# ESP8266_D1_Mini_Breakout.net
KiCad netlist of a schematic drawn in EAGLE
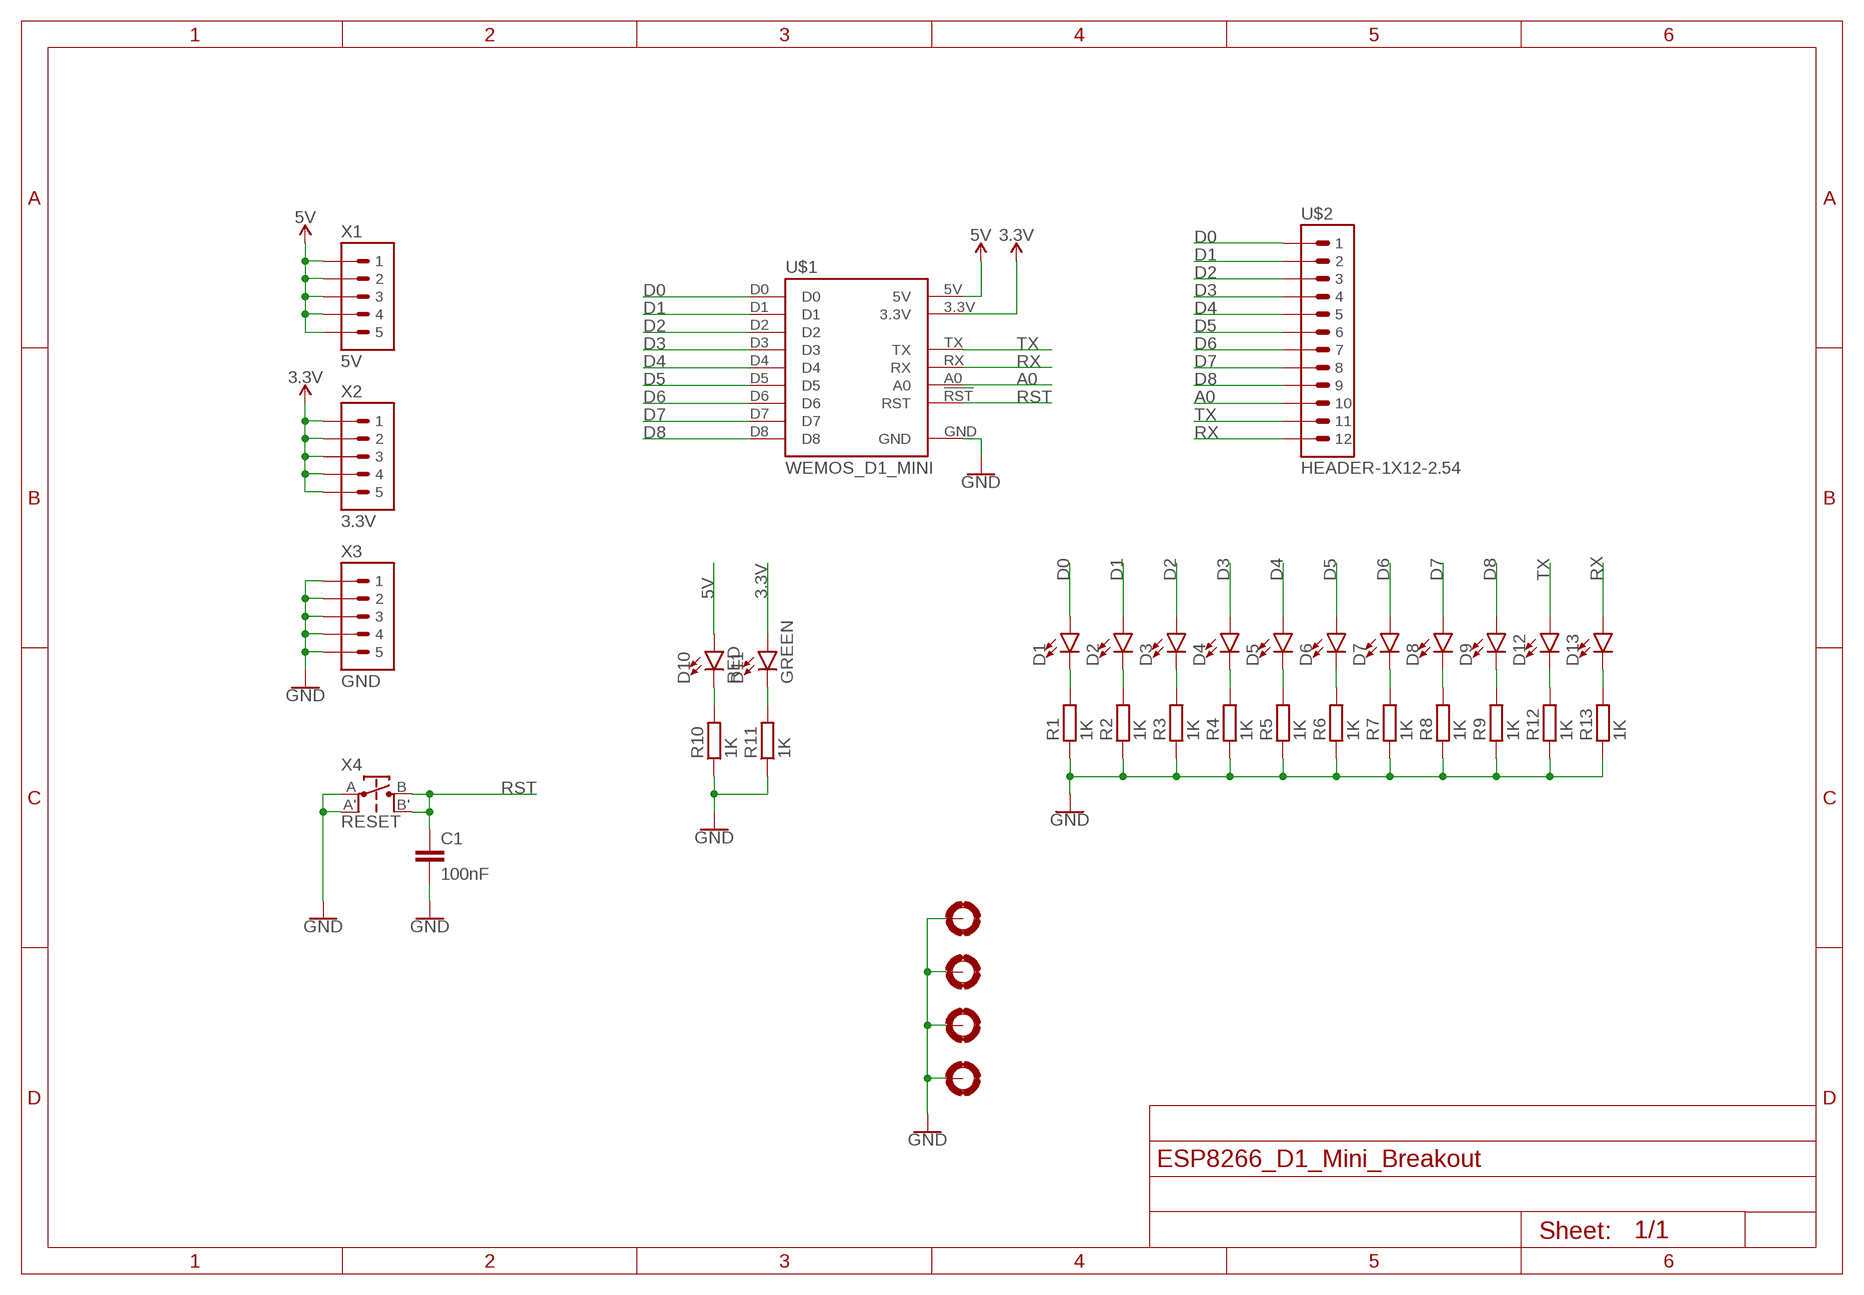
[diagram p0: schematic, sheet 1]

(export (version "E")
  (design (tool "Eeschema 10.0.6"))
  (components
    (comp (ref "C1")
      (value "100nF")
      (footprint "eagle-import:C0603")
      (libsource (lib "eagle-import") (part "CAPC0603"))
    )
    (comp (ref "D1")
      (value "LED0603")
      (footprint "eagle-import:LED0603")
      (libsource (lib "eagle-import") (part "LED0603"))
    )
    (comp (ref "D2")
      (value "LED0603")
      (footprint "eagle-import:LED0603")
      (libsource (lib "eagle-import") (part "LED0603"))
    )
    (comp (ref "D3")
      (value "LED0603")
      (footprint "eagle-import:LED0603")
      (libsource (lib "eagle-import") (part "LED0603"))
    )
    (comp (ref "D4")
      (value "LED0603")
      (footprint "eagle-import:LED0603")
      (libsource (lib "eagle-import") (part "LED0603"))
    )
    (comp (ref "D5")
      (value "LED0603")
      (footprint "eagle-import:LED0603")
      (libsource (lib "eagle-import") (part "LED0603"))
    )
    (comp (ref "D6")
      (value "LED0603")
      (footprint "eagle-import:LED0603")
      (libsource (lib "eagle-import") (part "LED0603"))
    )
    (comp (ref "D7")
      (value "LED0603")
      (footprint "eagle-import:LED0603")
      (libsource (lib "eagle-import") (part "LED0603"))
    )
    (comp (ref "D8")
      (value "LED0603")
      (footprint "eagle-import:LED0603")
      (libsource (lib "eagle-import") (part "LED0603"))
    )
    (comp (ref "D9")
      (value "LED0603")
      (footprint "eagle-import:LED0603")
      (libsource (lib "eagle-import") (part "LED0603"))
    )
    (comp (ref "D10")
      (value "RED")
      (footprint "eagle-import:LED0603")
      (libsource (lib "eagle-import") (part "LED0603"))
    )
    (comp (ref "D11")
      (value "GREEN")
      (footprint "eagle-import:LED0603")
      (libsource (lib "eagle-import") (part "LED0603"))
    )
    (comp (ref "D12")
      (value "LED0603")
      (footprint "eagle-import:LED0603")
      (libsource (lib "eagle-import") (part "LED0603"))
    )
    (comp (ref "D13")
      (value "LED0603")
      (footprint "eagle-import:LED0603")
      (libsource (lib "eagle-import") (part "LED0603"))
    )
    (comp (ref "H1")
      (value "MOUNTHOLE-PAD3.2")
      (footprint "eagle-import:3.2-PAD")
      (libsource (lib "eagle-import") (part "MOUNTHOLE-PAD3.2"))
    )
    (comp (ref "H2")
      (value "MOUNTHOLE-PAD3.2")
      (footprint "eagle-import:3.2-PAD")
      (libsource (lib "eagle-import") (part "MOUNTHOLE-PAD3.2"))
    )
    (comp (ref "H3")
      (value "MOUNTHOLE-PAD3.2")
      (footprint "eagle-import:3.2-PAD")
      (libsource (lib "eagle-import") (part "MOUNTHOLE-PAD3.2"))
    )
    (comp (ref "H4")
      (value "MOUNTHOLE-PAD3.2")
      (footprint "eagle-import:3.2-PAD")
      (libsource (lib "eagle-import") (part "MOUNTHOLE-PAD3.2"))
    )
    (comp (ref "R1")
      (value "1K")
      (footprint "eagle-import:R0603")
      (libsource (lib "eagle-import") (part "RESISTOR0603"))
    )
    (comp (ref "R2")
      (value "1K")
      (footprint "eagle-import:R0603")
      (libsource (lib "eagle-import") (part "RESISTOR0603"))
    )
    (comp (ref "R3")
      (value "1K")
      (footprint "eagle-import:R0603")
      (libsource (lib "eagle-import") (part "RESISTOR0603"))
    )
    (comp (ref "R4")
      (value "1K")
      (footprint "eagle-import:R0603")
      (libsource (lib "eagle-import") (part "RESISTOR0603"))
    )
    (comp (ref "R5")
      (value "1K")
      (footprint "eagle-import:R0603")
      (libsource (lib "eagle-import") (part "RESISTOR0603"))
    )
    (comp (ref "R6")
      (value "1K")
      (footprint "eagle-import:R0603")
      (libsource (lib "eagle-import") (part "RESISTOR0603"))
    )
    (comp (ref "R7")
      (value "1K")
      (footprint "eagle-import:R0603")
      (libsource (lib "eagle-import") (part "RESISTOR0603"))
    )
    (comp (ref "R8")
      (value "1K")
      (footprint "eagle-import:R0603")
      (libsource (lib "eagle-import") (part "RESISTOR0603"))
    )
    (comp (ref "R9")
      (value "1K")
      (footprint "eagle-import:R0603")
      (libsource (lib "eagle-import") (part "RESISTOR0603"))
    )
    (comp (ref "R10")
      (value "1K")
      (footprint "eagle-import:R0603")
      (libsource (lib "eagle-import") (part "RESISTOR0603"))
    )
    (comp (ref "R11")
      (value "1K")
      (footprint "eagle-import:R0603")
      (libsource (lib "eagle-import") (part "RESISTOR0603"))
    )
    (comp (ref "R12")
      (value "1K")
      (footprint "eagle-import:R0603")
      (libsource (lib "eagle-import") (part "RESISTOR0603"))
    )
    (comp (ref "R13")
      (value "1K")
      (footprint "eagle-import:R0603")
      (libsource (lib "eagle-import") (part "RESISTOR0603"))
    )
    (comp (ref "U$1")
      (value "WEMOS_D1_MINI")
      (footprint "eagle-import:WEMOS_D1_MINI")
      (libsource (lib "eagle-import") (part "WEMOS_D1_MINI"))
    )
    (comp (ref "U$2")
      (value "HEADER-1X12-2.54")
      (footprint "eagle-import:1X12-2.54")
      (libsource (lib "eagle-import") (part "HEADER-1X12-2.54"))
    )
    (comp (ref "X1")
      (value "5V")
      (footprint "eagle-import:1X05-2.54")
      (libsource (lib "eagle-import") (part "HEADER-1X05-2.54"))
    )
    (comp (ref "X2")
      (value "3.3V")
      (footprint "eagle-import:1X05-2.54")
      (libsource (lib "eagle-import") (part "HEADER-1X05-2.54"))
    )
    (comp (ref "X3")
      (value "GND")
      (footprint "eagle-import:1X05-2.54")
      (libsource (lib "eagle-import") (part "HEADER-1X05-2.54"))
    )
    (comp (ref "X4")
      (value "RESET")
      (footprint "eagle-import:TACT-SWITCH-EVQ")
      (libsource (lib "eagle-import") (part "TACT-SWITCHEVQ"))
    )
  )
  (nets
    (net (code "1") (name "/A0") (class "Default")
      (node (ref "U$1") (pin "A0") (pinfunction "A0_A0") (pintype "bidirectional"))
      (node (ref "U$2") (pin "10") (pinfunction "10_10") (pintype "bidirectional"))
    )
    (net (code "2") (name "/D0") (class "Default")
      (node (ref "D1") (pin "A") (pinfunction "A_A") (pintype "passive"))
      (node (ref "U$1") (pin "D0") (pinfunction "D0_D0") (pintype "bidirectional"))
      (node (ref "U$2") (pin "1") (pinfunction "1_1") (pintype "passive"))
    )
    (net (code "3") (name "/D1") (class "Default")
      (node (ref "D2") (pin "A") (pinfunction "A_A") (pintype "passive"))
      (node (ref "U$1") (pin "D1") (pinfunction "D1_D1") (pintype "bidirectional"))
      (node (ref "U$2") (pin "2") (pinfunction "2_2") (pintype "passive"))
    )
    (net (code "4") (name "/D2") (class "Default")
      (node (ref "D3") (pin "A") (pinfunction "A_A") (pintype "passive"))
      (node (ref "U$1") (pin "D2") (pinfunction "D2_D2") (pintype "bidirectional"))
      (node (ref "U$2") (pin "3") (pinfunction "3_3") (pintype "passive"))
    )
    (net (code "5") (name "/D3") (class "Default")
      (node (ref "D4") (pin "A") (pinfunction "A_A") (pintype "passive"))
      (node (ref "U$1") (pin "D3") (pinfunction "D3_D3") (pintype "bidirectional"))
      (node (ref "U$2") (pin "4") (pinfunction "4_4") (pintype "passive"))
    )
    (net (code "6") (name "/D4") (class "Default")
      (node (ref "D5") (pin "A") (pinfunction "A_A") (pintype "passive"))
      (node (ref "U$1") (pin "D4") (pinfunction "D4_D4") (pintype "bidirectional"))
      (node (ref "U$2") (pin "5") (pinfunction "5_5") (pintype "passive"))
    )
    (net (code "7") (name "/D5") (class "Default")
      (node (ref "D6") (pin "A") (pinfunction "A_A") (pintype "passive"))
      (node (ref "U$1") (pin "D5") (pinfunction "D5_D5") (pintype "bidirectional"))
      (node (ref "U$2") (pin "6") (pinfunction "6_6") (pintype "passive"))
    )
    (net (code "8") (name "/D6") (class "Default")
      (node (ref "D7") (pin "A") (pinfunction "A_A") (pintype "passive"))
      (node (ref "U$1") (pin "D6") (pinfunction "D6_D6") (pintype "bidirectional"))
      (node (ref "U$2") (pin "7") (pinfunction "7_7") (pintype "passive"))
    )
    (net (code "9") (name "/D7") (class "Default")
      (node (ref "D8") (pin "A") (pinfunction "A_A") (pintype "passive"))
      (node (ref "U$1") (pin "D7") (pinfunction "D7_D7") (pintype "bidirectional"))
      (node (ref "U$2") (pin "8") (pinfunction "8_8") (pintype "bidirectional"))
    )
    (net (code "10") (name "/D8") (class "Default")
      (node (ref "D9") (pin "A") (pinfunction "A_A") (pintype "passive"))
      (node (ref "U$1") (pin "D8") (pinfunction "D8_D8") (pintype "bidirectional"))
      (node (ref "U$2") (pin "9") (pinfunction "9_9") (pintype "bidirectional"))
    )
    (net (code "11") (name "/RST") (class "Default")
      (node (ref "C1") (pin "1") (pinfunction "1_1") (pintype "passive"))
      (node (ref "U$1") (pin "!RST") (pinfunction "RST_!RST") (pintype "bidirectional"))
      (node (ref "X4") (pin "B") (pinfunction "B_B") (pintype "bidirectional"))
      (node (ref "X4") (pin "B'") (pinfunction "B'_B'") (pintype "bidirectional"))
    )
    (net (code "12") (name "/RX") (class "Default")
      (node (ref "D13") (pin "A") (pinfunction "A_A") (pintype "passive"))
      (node (ref "U$1") (pin "RX") (pinfunction "RX_RX") (pintype "bidirectional"))
      (node (ref "U$2") (pin "12") (pinfunction "12_12") (pintype "bidirectional"))
    )
    (net (code "13") (name "/TX") (class "Default")
      (node (ref "D12") (pin "A") (pinfunction "A_A") (pintype "passive"))
      (node (ref "U$1") (pin "TX") (pinfunction "TX_TX") (pintype "bidirectional"))
      (node (ref "U$2") (pin "11") (pinfunction "11_11") (pintype "bidirectional"))
    )
    (net (code "14") (name "3.3V") (class "Default")
      (node (ref "D11") (pin "A") (pinfunction "A_A") (pintype "passive"))
      (node (ref "U$1") (pin "3.3V") (pinfunction "3.3V_3.3V") (pintype "bidirectional"))
      (node (ref "X2") (pin "1") (pinfunction "1_1") (pintype "passive"))
      (node (ref "X2") (pin "2") (pinfunction "2_2") (pintype "passive"))
      (node (ref "X2") (pin "3") (pinfunction "3_3") (pintype "passive"))
      (node (ref "X2") (pin "4") (pinfunction "4_4") (pintype "passive"))
      (node (ref "X2") (pin "5") (pinfunction "5_5") (pintype "passive"))
    )
    (net (code "15") (name "5V") (class "Default")
      (node (ref "D10") (pin "A") (pinfunction "A_A") (pintype "passive"))
      (node (ref "U$1") (pin "5V") (pinfunction "5V_5V") (pintype "bidirectional"))
      (node (ref "X1") (pin "1") (pinfunction "1_1") (pintype "passive"))
      (node (ref "X1") (pin "2") (pinfunction "2_2") (pintype "passive"))
      (node (ref "X1") (pin "3") (pinfunction "3_3") (pintype "passive"))
      (node (ref "X1") (pin "4") (pinfunction "4_4") (pintype "passive"))
      (node (ref "X1") (pin "5") (pinfunction "5_5") (pintype "passive"))
    )
    (net (code "16") (name "GND") (class "Default")
      (node (ref "C1") (pin "2") (pinfunction "2_2") (pintype "passive"))
      (node (ref "H1") (pin "B3,2") (pinfunction "MOUNT_B3,2") (pintype "passive"))
      (node (ref "H2") (pin "B3,2") (pinfunction "MOUNT_B3,2") (pintype "passive"))
      (node (ref "H3") (pin "B3,2") (pinfunction "MOUNT_B3,2") (pintype "passive"))
      (node (ref "H4") (pin "B3,2") (pinfunction "MOUNT_B3,2") (pintype "passive"))
      (node (ref "R1") (pin "1") (pinfunction "1_1") (pintype "passive"))
      (node (ref "R10") (pin "1") (pinfunction "1_1") (pintype "passive"))
      (node (ref "R11") (pin "1") (pinfunction "1_1") (pintype "passive"))
      (node (ref "R12") (pin "1") (pinfunction "1_1") (pintype "passive"))
      (node (ref "R13") (pin "1") (pinfunction "1_1") (pintype "passive"))
      (node (ref "R2") (pin "1") (pinfunction "1_1") (pintype "passive"))
      (node (ref "R3") (pin "1") (pinfunction "1_1") (pintype "passive"))
      (node (ref "R4") (pin "1") (pinfunction "1_1") (pintype "passive"))
      (node (ref "R5") (pin "1") (pinfunction "1_1") (pintype "passive"))
      (node (ref "R6") (pin "1") (pinfunction "1_1") (pintype "passive"))
      (node (ref "R7") (pin "1") (pinfunction "1_1") (pintype "passive"))
      (node (ref "R8") (pin "1") (pinfunction "1_1") (pintype "passive"))
      (node (ref "R9") (pin "1") (pinfunction "1_1") (pintype "passive"))
      (node (ref "U$1") (pin "GND") (pinfunction "GND_GND") (pintype "bidirectional"))
      (node (ref "X3") (pin "1") (pinfunction "1_1") (pintype "passive"))
      (node (ref "X3") (pin "2") (pinfunction "2_2") (pintype "passive"))
      (node (ref "X3") (pin "3") (pinfunction "3_3") (pintype "passive"))
      (node (ref "X3") (pin "4") (pinfunction "4_4") (pintype "passive"))
      (node (ref "X3") (pin "5") (pinfunction "5_5") (pintype "passive"))
      (node (ref "X4") (pin "A") (pinfunction "A_A") (pintype "bidirectional"))
      (node (ref "X4") (pin "A'") (pinfunction "A'_A'") (pintype "bidirectional"))
    )
    (net (code "17") (name "Net-(D1-PadC)") (class "Default")
      (node (ref "D1") (pin "C") (pinfunction "C_C") (pintype "passive"))
      (node (ref "R1") (pin "2") (pinfunction "2_2") (pintype "passive"))
    )
    (net (code "18") (name "Net-(D2-PadC)") (class "Default")
      (node (ref "D2") (pin "C") (pinfunction "C_C") (pintype "passive"))
      (node (ref "R2") (pin "2") (pinfunction "2_2") (pintype "passive"))
    )
    (net (code "19") (name "Net-(D3-PadC)") (class "Default")
      (node (ref "D3") (pin "C") (pinfunction "C_C") (pintype "passive"))
      (node (ref "R3") (pin "2") (pinfunction "2_2") (pintype "passive"))
    )
    (net (code "20") (name "Net-(D4-PadC)") (class "Default")
      (node (ref "D4") (pin "C") (pinfunction "C_C") (pintype "passive"))
      (node (ref "R4") (pin "2") (pinfunction "2_2") (pintype "passive"))
    )
    (net (code "21") (name "Net-(D5-PadC)") (class "Default")
      (node (ref "D5") (pin "C") (pinfunction "C_C") (pintype "passive"))
      (node (ref "R5") (pin "2") (pinfunction "2_2") (pintype "passive"))
    )
    (net (code "22") (name "Net-(D6-PadC)") (class "Default")
      (node (ref "D6") (pin "C") (pinfunction "C_C") (pintype "passive"))
      (node (ref "R6") (pin "2") (pinfunction "2_2") (pintype "passive"))
    )
    (net (code "23") (name "Net-(D7-PadC)") (class "Default")
      (node (ref "D7") (pin "C") (pinfunction "C_C") (pintype "passive"))
      (node (ref "R7") (pin "2") (pinfunction "2_2") (pintype "passive"))
    )
    (net (code "24") (name "Net-(D8-PadC)") (class "Default")
      (node (ref "D8") (pin "C") (pinfunction "C_C") (pintype "passive"))
      (node (ref "R8") (pin "2") (pinfunction "2_2") (pintype "passive"))
    )
    (net (code "25") (name "Net-(D9-PadC)") (class "Default")
      (node (ref "D9") (pin "C") (pinfunction "C_C") (pintype "passive"))
      (node (ref "R9") (pin "2") (pinfunction "2_2") (pintype "passive"))
    )
    (net (code "26") (name "Net-(D10-PadC)") (class "Default")
      (node (ref "D10") (pin "C") (pinfunction "C_C") (pintype "passive"))
      (node (ref "R10") (pin "2") (pinfunction "2_2") (pintype "passive"))
    )
    (net (code "27") (name "Net-(D11-PadC)") (class "Default")
      (node (ref "D11") (pin "C") (pinfunction "C_C") (pintype "passive"))
      (node (ref "R11") (pin "2") (pinfunction "2_2") (pintype "passive"))
    )
    (net (code "28") (name "Net-(D12-PadC)") (class "Default")
      (node (ref "D12") (pin "C") (pinfunction "C_C") (pintype "passive"))
      (node (ref "R12") (pin "2") (pinfunction "2_2") (pintype "passive"))
    )
    (net (code "29") (name "Net-(D13-PadC)") (class "Default")
      (node (ref "D13") (pin "C") (pinfunction "C_C") (pintype "passive"))
      (node (ref "R13") (pin "2") (pinfunction "2_2") (pintype "passive"))
    )
  )
)
